# FRONT.net
KiCad netlist of a schematic drawn in Altium Designer
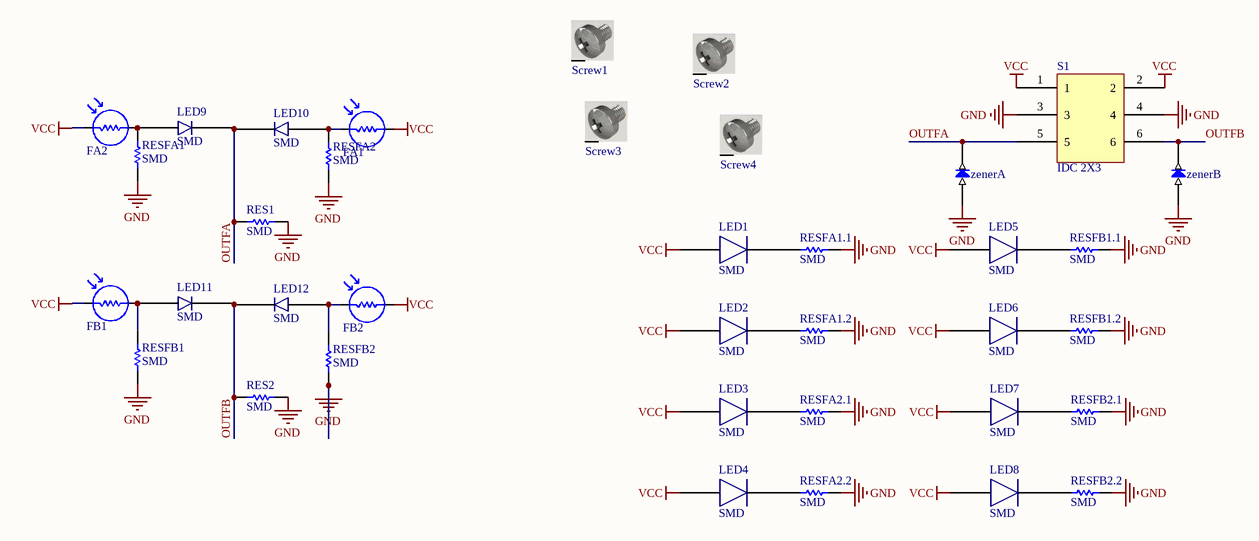
[diagram p0: FRONT.SchDoc]

(export (version "E")
  (design (tool "Eeschema 10.0.6"))
  (components
    (comp (ref "FA1")
      (value "Photo Cell")
      (footprint "PhotoCell.")
      (fields (field (name "PUBLISHER") "Altium Limited"))
      (libsource (lib "Farzanegan") (part "Photo Cell.."))
    )
    (comp (ref "FA2")
      (value "Photo Cell")
      (footprint "PhotoCell.")
      (fields (field (name "PUBLISHER") "Altium Limited"))
      (libsource (lib "Farzanegan") (part "Photo Cell.."))
    )
    (comp (ref "FB1")
      (value "Photo Cell")
      (footprint "PhotoCell.")
      (fields (field (name "PUBLISHER") "Altium Limited"))
      (libsource (lib "Farzanegan") (part "Photo Cell.."))
    )
    (comp (ref "FB2")
      (value "Photo Cell")
      (footprint "PhotoCell.")
      (fields (field (name "PUBLISHER") "Altium Limited"))
      (libsource (lib "Farzanegan") (part "Photo Cell.."))
    )
    (comp (ref "LED1") (value "SMD") (footprint "LED SMD") (libsource (lib "") (part "LED SMD_1")))
    (comp (ref "LED2") (value "SMD") (footprint "LED SMD") (libsource (lib "") (part "LED SMD_1")))
    (comp (ref "LED3") (value "SMD") (footprint "LED SMD") (libsource (lib "") (part "LED SMD_1")))
    (comp (ref "LED4") (value "SMD") (footprint "LED SMD") (libsource (lib "") (part "LED SMD_1")))
    (comp (ref "LED5") (value "SMD") (footprint "LED SMD") (libsource (lib "") (part "LED SMD_1")))
    (comp (ref "LED6") (value "SMD") (footprint "LED SMD") (libsource (lib "") (part "LED SMD_1")))
    (comp (ref "LED7") (value "SMD") (footprint "LED SMD") (libsource (lib "") (part "LED SMD_1")))
    (comp (ref "LED8") (value "SMD") (footprint "LED SMD") (libsource (lib "") (part "LED SMD_1")))
    (comp (ref "LED9") (value "SMD") (footprint "LED SMD") (libsource (lib "Farzanegan") (part "LED SMD")))
    (comp (ref "LED10") (value "SMD") (footprint "LED SMD") (libsource (lib "Farzanegan") (part "LED SMD")))
    (comp (ref "LED11") (value "SMD") (footprint "LED SMD") (libsource (lib "Farzanegan") (part "LED SMD")))
    (comp (ref "LED12") (value "SMD") (footprint "LED SMD") (libsource (lib "Farzanegan") (part "LED SMD")))
    (comp (ref "RES1")
      (value "SMD")
      (footprint "Resistor SMD 1206")
      (libsource (lib "Farzanegan") (part "Res SMD"))
    )
    (comp (ref "RES2")
      (value "SMD")
      (footprint "Resistor SMD 1206")
      (libsource (lib "Farzanegan") (part "Res SMD"))
    )
    (comp (ref "RESFA1")
      (value "SMD")
      (footprint "Resistor SMD 1206")
      (libsource (lib "Farzanegan") (part "Res SMD"))
    )
    (comp (ref "RESFA1.1")
      (value "SMD")
      (footprint "Resistor SMD 1206")
      (libsource (lib "Farzanegan") (part "Res SMD"))
    )
    (comp (ref "RESFA1.2")
      (value "SMD")
      (footprint "Resistor SMD 1206")
      (libsource (lib "Farzanegan") (part "Res SMD"))
    )
    (comp (ref "RESFA2")
      (value "SMD")
      (footprint "Resistor SMD 1206")
      (libsource (lib "Farzanegan") (part "Res SMD"))
    )
    (comp (ref "RESFA2.1")
      (value "SMD")
      (footprint "Resistor SMD 1206")
      (libsource (lib "Farzanegan") (part "Res SMD"))
    )
    (comp (ref "RESFA2.2")
      (value "SMD")
      (footprint "Resistor SMD 1206")
      (libsource (lib "Farzanegan") (part "Res SMD"))
    )
    (comp (ref "RESFB1")
      (value "SMD")
      (footprint "Resistor SMD 1206")
      (libsource (lib "Farzanegan") (part "Res SMD"))
    )
    (comp (ref "RESFB1.1")
      (value "SMD")
      (footprint "Resistor SMD 1206")
      (libsource (lib "Farzanegan") (part "Res SMD"))
    )
    (comp (ref "RESFB1.2")
      (value "SMD")
      (footprint "Resistor SMD 1206")
      (libsource (lib "Farzanegan") (part "Res SMD"))
    )
    (comp (ref "RESFB2")
      (value "SMD")
      (footprint "Resistor SMD 1206")
      (libsource (lib "Farzanegan") (part "Res SMD"))
    )
    (comp (ref "RESFB2.1")
      (value "SMD")
      (footprint "Resistor SMD 1206")
      (libsource (lib "Farzanegan") (part "Res SMD"))
    )
    (comp (ref "RESFB2.2")
      (value "SMD")
      (footprint "Resistor SMD 1206")
      (libsource (lib "Farzanegan") (part "Res SMD"))
    )
    (comp (ref "S1") (value "IDC 2X3") (footprint "IDC 2X3") (libsource (lib "Farzanegan") (part "IDC 2X3")))
    (comp (ref "Screw1")
      (value "Screw")
      (footprint "Screw")
      (fields (field (name "PUBLISHER") "Altium Limited"))
      (libsource (lib "Farzanegan") (part "Screw"))
    )
    (comp (ref "Screw2")
      (value "Screw")
      (footprint "Screw")
      (fields (field (name "PUBLISHER") "Altium Limited"))
      (libsource (lib "Farzanegan") (part "Screw"))
    )
    (comp (ref "Screw3")
      (value "Screw")
      (footprint "Screw")
      (fields (field (name "PUBLISHER") "Altium Limited"))
      (libsource (lib "Farzanegan") (part "Screw"))
    )
    (comp (ref "Screw4")
      (value "Screw")
      (footprint "Screw")
      (fields (field (name "PUBLISHER") "Altium Limited"))
      (libsource (lib "Farzanegan") (part "Screw"))
    )
    (comp (ref "zenerA")
      (value "zener")
      (footprint "LED SMD")
      (libsource (lib "Farz1") (part "SMDZenerDiode"))
    )
    (comp (ref "zenerB")
      (value "zener")
      (footprint "LED SMD")
      (libsource (lib "Farz1") (part "SMDZenerDiode"))
    )
  )
  (nets
    (net (code "1") (name "/OUTFA") (class "Default")
      (node (ref "LED10") (pin "2") (pinfunction "2_2") (pintype "passive"))
      (node (ref "LED9") (pin "2") (pinfunction "2_2") (pintype "passive"))
      (node (ref "RES1") (pin "1") (pinfunction "1_1") (pintype "passive"))
      (node (ref "S1") (pin "5") (pinfunction "5_5") (pintype "passive"))
      (node (ref "zenerA") (pin "2") (pinfunction "out_2") (pintype "output"))
    )
    (net (code "2") (name "/OUTFB") (class "Default")
      (node (ref "LED11") (pin "2") (pinfunction "2_2") (pintype "passive"))
      (node (ref "LED12") (pin "2") (pinfunction "2_2") (pintype "passive"))
      (node (ref "RES2") (pin "1") (pinfunction "1_1") (pintype "passive"))
      (node (ref "S1") (pin "6") (pinfunction "6_6") (pintype "passive"))
      (node (ref "zenerB") (pin "2") (pinfunction "out_2") (pintype "output"))
    )
    (net (code "3") (name "GND") (class "Default")
      (node (ref "RES1") (pin "2") (pinfunction "2_2") (pintype "passive"))
      (node (ref "RES2") (pin "2") (pinfunction "2_2") (pintype "passive"))
      (node (ref "RESFA1") (pin "1") (pinfunction "1_1") (pintype "passive"))
      (node (ref "RESFA1.1") (pin "2") (pinfunction "2_2") (pintype "passive"))
      (node (ref "RESFA1.2") (pin "2") (pinfunction "2_2") (pintype "passive"))
      (node (ref "RESFA2") (pin "1") (pinfunction "1_1") (pintype "passive"))
      (node (ref "RESFA2.1") (pin "2") (pinfunction "2_2") (pintype "passive"))
      (node (ref "RESFA2.2") (pin "2") (pinfunction "2_2") (pintype "passive"))
      (node (ref "RESFB1") (pin "1") (pinfunction "1_1") (pintype "passive"))
      (node (ref "RESFB1.1") (pin "2") (pinfunction "2_2") (pintype "passive"))
      (node (ref "RESFB1.2") (pin "2") (pinfunction "2_2") (pintype "passive"))
      (node (ref "RESFB2") (pin "1") (pinfunction "1_1") (pintype "passive"))
      (node (ref "RESFB2.1") (pin "2") (pinfunction "2_2") (pintype "passive"))
      (node (ref "RESFB2.2") (pin "2") (pinfunction "2_2") (pintype "passive"))
      (node (ref "S1") (pin "3") (pinfunction "3_3") (pintype "passive"))
      (node (ref "S1") (pin "4") (pinfunction "4_4") (pintype "passive"))
      (node (ref "zenerA") (pin "1") (pinfunction "in_1") (pintype "input"))
      (node (ref "zenerB") (pin "1") (pinfunction "in_1") (pintype "input"))
    )
    (net (code "4") (name "Net-(FA1-Pad1)") (class "Default")
      (node (ref "FA1") (pin "1") (pintype "passive"))
      (node (ref "LED10") (pin "1") (pinfunction "1_1") (pintype "passive"))
      (node (ref "RESFA2") (pin "2") (pinfunction "2_2") (pintype "passive"))
    )
    (net (code "5") (name "Net-(FA2-Pad2)") (class "Default")
      (node (ref "FA2") (pin "2") (pintype "passive"))
      (node (ref "LED9") (pin "1") (pinfunction "1_1") (pintype "passive"))
      (node (ref "RESFA1") (pin "2") (pinfunction "2_2") (pintype "passive"))
    )
    (net (code "6") (name "Net-(FB1-Pad2)") (class "Default")
      (node (ref "FB1") (pin "2") (pintype "passive"))
      (node (ref "LED11") (pin "1") (pinfunction "1_1") (pintype "passive"))
      (node (ref "RESFB1") (pin "2") (pinfunction "2_2") (pintype "passive"))
    )
    (net (code "7") (name "Net-(FB2-Pad1)") (class "Default")
      (node (ref "FB2") (pin "1") (pintype "passive"))
      (node (ref "LED12") (pin "1") (pinfunction "1_1") (pintype "passive"))
      (node (ref "RESFB2") (pin "2") (pinfunction "2_2") (pintype "passive"))
    )
    (net (code "8") (name "Net-(LED1-Pad2)") (class "Default")
      (node (ref "LED1") (pin "2") (pinfunction "2_2") (pintype "passive"))
      (node (ref "RESFA1.1") (pin "1") (pinfunction "1_1") (pintype "passive"))
    )
    (net (code "9") (name "Net-(LED2-Pad2)") (class "Default")
      (node (ref "LED2") (pin "2") (pinfunction "2_2") (pintype "passive"))
      (node (ref "RESFA1.2") (pin "1") (pinfunction "1_1") (pintype "passive"))
    )
    (net (code "10") (name "Net-(LED3-Pad2)") (class "Default")
      (node (ref "LED3") (pin "2") (pinfunction "2_2") (pintype "passive"))
      (node (ref "RESFA2.1") (pin "1") (pinfunction "1_1") (pintype "passive"))
    )
    (net (code "11") (name "Net-(LED4-Pad2)") (class "Default")
      (node (ref "LED4") (pin "2") (pinfunction "2_2") (pintype "passive"))
      (node (ref "RESFA2.2") (pin "1") (pinfunction "1_1") (pintype "passive"))
    )
    (net (code "12") (name "Net-(LED5-Pad2)") (class "Default")
      (node (ref "LED5") (pin "2") (pinfunction "2_2") (pintype "passive"))
      (node (ref "RESFB1.1") (pin "1") (pinfunction "1_1") (pintype "passive"))
    )
    (net (code "13") (name "Net-(LED6-Pad2)") (class "Default")
      (node (ref "LED6") (pin "2") (pinfunction "2_2") (pintype "passive"))
      (node (ref "RESFB1.2") (pin "1") (pinfunction "1_1") (pintype "passive"))
    )
    (net (code "14") (name "Net-(LED7-Pad2)") (class "Default")
      (node (ref "LED7") (pin "2") (pinfunction "2_2") (pintype "passive"))
      (node (ref "RESFB2.1") (pin "1") (pinfunction "1_1") (pintype "passive"))
    )
    (net (code "15") (name "Net-(LED8-Pad2)") (class "Default")
      (node (ref "LED8") (pin "2") (pinfunction "2_2") (pintype "passive"))
      (node (ref "RESFB2.2") (pin "1") (pinfunction "1_1") (pintype "passive"))
    )
    (net (code "16") (name "VCC") (class "Default")
      (node (ref "FA1") (pin "2") (pintype "passive"))
      (node (ref "FA2") (pin "1") (pintype "passive"))
      (node (ref "FB1") (pin "1") (pintype "passive"))
      (node (ref "FB2") (pin "2") (pintype "passive"))
      (node (ref "LED1") (pin "1") (pinfunction "1_1") (pintype "passive"))
      (node (ref "LED2") (pin "1") (pinfunction "1_1") (pintype "passive"))
      (node (ref "LED3") (pin "1") (pinfunction "1_1") (pintype "passive"))
      (node (ref "LED4") (pin "1") (pinfunction "1_1") (pintype "passive"))
      (node (ref "LED5") (pin "1") (pinfunction "1_1") (pintype "passive"))
      (node (ref "LED6") (pin "1") (pinfunction "1_1") (pintype "passive"))
      (node (ref "LED7") (pin "1") (pinfunction "1_1") (pintype "passive"))
      (node (ref "LED8") (pin "1") (pinfunction "1_1") (pintype "passive"))
      (node (ref "S1") (pin "1") (pinfunction "1_1") (pintype "passive"))
      (node (ref "S1") (pin "2") (pinfunction "2_2") (pintype "passive"))
    )
    (net (code "17") (name "unconnected-(Screw1-PadS)") (class "Default")
      (node (ref "Screw1") (pin "S") (pinfunction "S_S") (pintype "passive"))
    )
    (net (code "18") (name "unconnected-(Screw2-PadS)") (class "Default")
      (node (ref "Screw2") (pin "S") (pinfunction "S_S") (pintype "passive"))
    )
    (net (code "19") (name "unconnected-(Screw3-PadS)") (class "Default")
      (node (ref "Screw3") (pin "S") (pinfunction "S_S") (pintype "passive"))
    )
    (net (code "20") (name "unconnected-(Screw4-PadS)") (class "Default")
      (node (ref "Screw4") (pin "S") (pinfunction "S_S") (pintype "passive"))
    )
  )
)
